# -2.net
KiCad netlist of a schematic drawn in Altium Designer
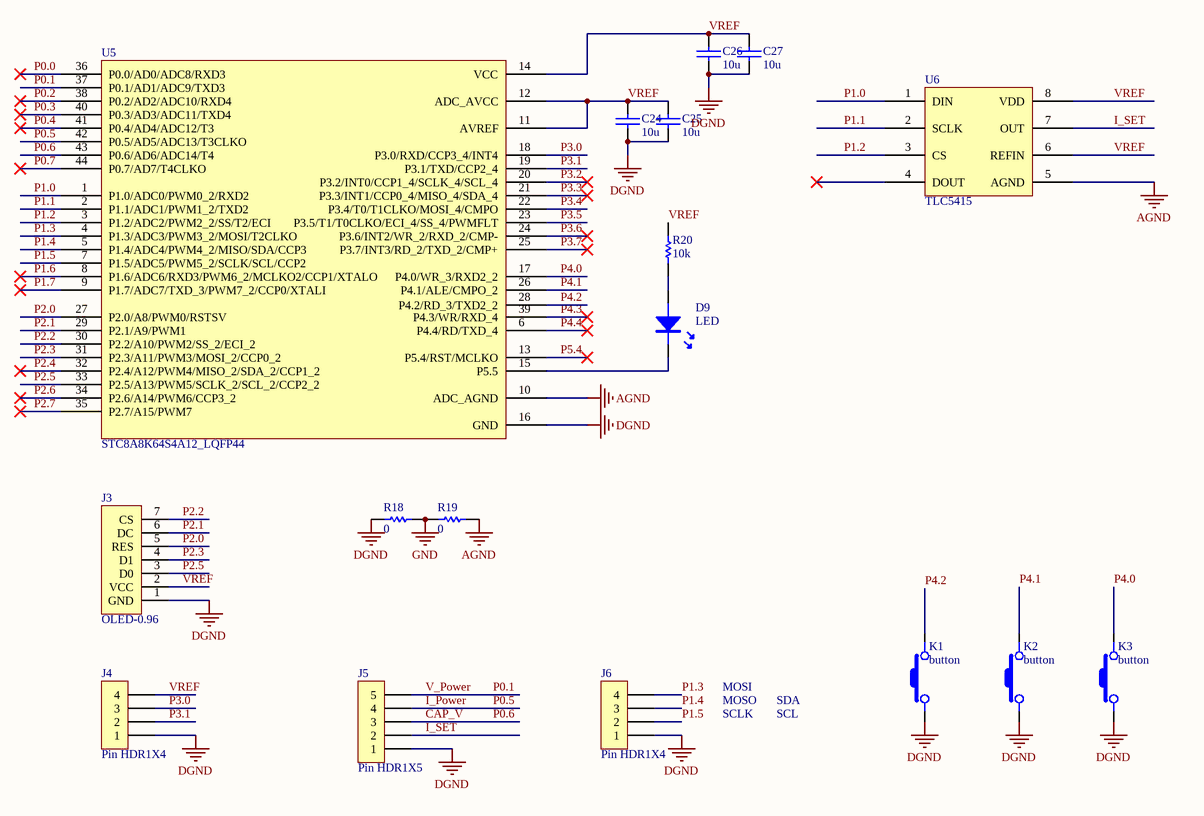
[diagram p0: 充电二板-2.SchDoc]

(export (version "E")
  (design (tool "Eeschema 10.0.6"))
  (components
    (comp (ref "C24")
      (value "10u")
      (footprint "0603C")
      (description "无极性电容")
      (libsource (lib "电容") (part "CAP"))
    )
    (comp (ref "C25")
      (value "10u")
      (footprint "0603C")
      (description "无极性电容")
      (libsource (lib "电容") (part "CAP"))
    )
    (comp (ref "C26")
      (value "10u")
      (footprint "0603C")
      (description "无极性电容")
      (libsource (lib "电容") (part "CAP"))
    )
    (comp (ref "C27")
      (value "10u")
      (footprint "0603C")
      (description "无极性电容")
      (libsource (lib "电容") (part "CAP"))
    )
    (comp (ref "D9") (value "LED") (footprint "LED-0603W") (libsource (lib "LED") (part "LED")))
    (comp (ref "J3")
      (value "OLED-0.96")
      (footprint "OLED-0.96")
      (libsource (lib "KEA电磁专用") (part "OLED-0.96"))
    )
    (comp (ref "J4")
      (value "Pin HDR1X4")
      (footprint "Pin HDR1X4/2.54mm-S")
      (libsource (lib "排针") (part "Pin HDR1X4"))
    )
    (comp (ref "J5")
      (value "Pin HDR1X5")
      (footprint "Pin HDR1X5/2.54mm-S")
      (libsource (lib "排针") (part "Pin HDR1X5"))
    )
    (comp (ref "J6")
      (value "Pin HDR1X4")
      (footprint "Pin HDR1X4/2.54mm-S")
      (libsource (lib "排针") (part "Pin HDR1X4"))
    )
    (comp (ref "K1") (value "button") (footprint "button") (libsource (lib "charge") (part "button")))
    (comp (ref "K2") (value "button") (footprint "button") (libsource (lib "charge") (part "button")))
    (comp (ref "K3") (value "button") (footprint "button") (libsource (lib "charge") (part "button")))
    (comp (ref "R18") (value "0") (footprint "0603R") (libsource (lib "电阻") (part "RES")))
    (comp (ref "R19") (value "0") (footprint "0603R") (libsource (lib "电阻") (part "RES")))
    (comp (ref "R20") (value "10k") (footprint "0603R") (libsource (lib "电阻") (part "RES")))
    (comp (ref "U5")
      (value "STC8A8K64S4A12_LQFP44")
      (footprint "LQFP144")
      (libsource (lib "charge") (part "STC8A8K64S4A12_LQFP44"))
    )
    (comp (ref "U6") (value "TLC5415") (footprint "TLC5415") (libsource (lib "charge") (part "TLC5415")))
  )
  (nets
    (net (code "1") (name "/CAP_V") (class "Default")
      (node (ref "J5") (pin "3") (pinfunction "3_3") (pintype "passive"))
      (node (ref "U5") (pin "43") (pinfunction "P0.6/AD6/ADC14/T4_43") (pintype "passive"))
    )
    (net (code "2") (name "/I_Power") (class "Default")
      (node (ref "J5") (pin "4") (pinfunction "4_4") (pintype "passive"))
      (node (ref "U5") (pin "42") (pinfunction "P0.5/AD5/ADC13/T3CLKO_42") (pintype "passive"))
    )
    (net (code "3") (name "/I_SET") (class "Default")
      (node (ref "J5") (pin "2") (pinfunction "2_2") (pintype "passive"))
      (node (ref "U6") (pin "7") (pinfunction "OUT_7") (pintype "passive"))
    )
    (net (code "4") (name "/P0.0") (class "Default")
      (node (ref "U5") (pin "36") (pinfunction "P0.0/AD0/ADC8/RXD3_36") (pintype "passive+no_connect"))
    )
    (net (code "5") (name "/P0.1") (class "Default")
      (node (ref "J5") (pin "5") (pinfunction "5_5") (pintype "passive"))
      (node (ref "U5") (pin "37") (pinfunction "P0.1/AD1/ADC9/TXD3_37") (pintype "passive"))
    )
    (net (code "6") (name "/P0.2") (class "Default")
      (node (ref "U5") (pin "38") (pinfunction "P0.2/AD2/ADC10/RXD4_38") (pintype "passive+no_connect"))
    )
    (net (code "7") (name "/P0.3") (class "Default")
      (node (ref "U5") (pin "40") (pinfunction "P0.3/AD3/ADC11/TXD4_40") (pintype "passive+no_connect"))
    )
    (net (code "8") (name "/P0.4") (class "Default")
      (node (ref "U5") (pin "41") (pinfunction "P0.4/AD4/ADC12/T3_41") (pintype "passive+no_connect"))
    )
    (net (code "9") (name "/P0.7") (class "Default")
      (node (ref "U5") (pin "44") (pinfunction "P0.7/AD7/T4CLKO_44") (pintype "passive+no_connect"))
    )
    (net (code "10") (name "/P1.0") (class "Default")
      (node (ref "U5") (pin "1") (pinfunction "P1.0/ADC0/PWM0_2/RXD2_1") (pintype "passive"))
      (node (ref "U6") (pin "1") (pinfunction "DIN_1") (pintype "passive"))
    )
    (net (code "11") (name "/P1.1") (class "Default")
      (node (ref "U5") (pin "2") (pinfunction "P1.1/ADC1/PWM1_2/TXD2_2") (pintype "passive"))
      (node (ref "U6") (pin "2") (pinfunction "SCLK_2") (pintype "passive"))
    )
    (net (code "12") (name "/P1.2") (class "Default")
      (node (ref "U5") (pin "3") (pinfunction "P1.2/ADC2/PWM2_2/SS/T2/ECI_3") (pintype "passive"))
      (node (ref "U6") (pin "3") (pinfunction "CS_3") (pintype "passive"))
    )
    (net (code "13") (name "/P1.3") (class "Default")
      (node (ref "J6") (pin "4") (pinfunction "4_4") (pintype "passive"))
      (node (ref "U5") (pin "4") (pinfunction "P1.3/ADC3/PWM3_2/MOSI/T2CLKO_4") (pintype "passive"))
    )
    (net (code "14") (name "/P1.4") (class "Default")
      (node (ref "J6") (pin "3") (pinfunction "3_3") (pintype "passive"))
      (node (ref "U5") (pin "5") (pinfunction "P1.4/ADC4/PWM4_2/MISO/SDA/CCP3_5") (pintype "passive"))
    )
    (net (code "15") (name "/P1.5") (class "Default")
      (node (ref "J6") (pin "2") (pinfunction "2_2") (pintype "passive"))
      (node (ref "U5") (pin "7") (pinfunction "P1.5/ADC5/PWM5_2/SCLK/SCL/CCP2_7") (pintype "passive"))
    )
    (net (code "16") (name "/P1.6") (class "Default")
      (node (ref "U5") (pin "8") (pinfunction "P1.6/ADC6/RXD3/PWM6_2/MCLKO2/CCP1/XTALO_8") (pintype "passive+no_connect"))
    )
    (net (code "17") (name "/P1.7") (class "Default")
      (node (ref "U5") (pin "9") (pinfunction "P1.7/ADC7/TXD_3/PWM7_2/CCP0/XTALI_9") (pintype "passive+no_connect"))
    )
    (net (code "18") (name "/P2.0") (class "Default")
      (node (ref "J3") (pin "5") (pinfunction "RES_5") (pintype "passive"))
      (node (ref "U5") (pin "27") (pinfunction "P2.0/A8/PWM0/RSTSV_27") (pintype "passive"))
    )
    (net (code "19") (name "/P2.1") (class "Default")
      (node (ref "J3") (pin "6") (pinfunction "DC_6") (pintype "passive"))
      (node (ref "U5") (pin "29") (pinfunction "P2.1/A9/PWM1_29") (pintype "passive"))
    )
    (net (code "20") (name "/P2.2") (class "Default")
      (node (ref "J3") (pin "7") (pinfunction "CS_7") (pintype "passive"))
      (node (ref "U5") (pin "30") (pinfunction "P2.2/A10/PWM2/SS_2/ECI_2_30") (pintype "passive"))
    )
    (net (code "21") (name "/P2.3") (class "Default")
      (node (ref "J3") (pin "4") (pinfunction "D1_4") (pintype "passive"))
      (node (ref "U5") (pin "31") (pinfunction "P2.3/A11/PWM3/MOSI_2/CCP0_2_31") (pintype "passive"))
    )
    (net (code "22") (name "/P2.4") (class "Default")
      (node (ref "U5") (pin "32") (pinfunction "P2.4/A12/PWM4/MISO_2/SDA_2/CCP1_2_32") (pintype "passive+no_connect"))
    )
    (net (code "23") (name "/P2.5") (class "Default")
      (node (ref "J3") (pin "3") (pinfunction "D0_3") (pintype "passive"))
      (node (ref "U5") (pin "33") (pinfunction "P2.5/A13/PWM5/SCLK_2/SCL_2/CCP2_2_33") (pintype "passive"))
    )
    (net (code "24") (name "/P2.6") (class "Default")
      (node (ref "U5") (pin "34") (pinfunction "P2.6/A14/PWM6/CCP3_2_34") (pintype "passive+no_connect"))
    )
    (net (code "25") (name "/P2.7") (class "Default")
      (node (ref "U5") (pin "35") (pinfunction "P2.7/A15/PWM7_35") (pintype "passive+no_connect"))
    )
    (net (code "26") (name "/P3.0") (class "Default")
      (node (ref "J4") (pin "3") (pinfunction "3_3") (pintype "passive"))
      (node (ref "U5") (pin "18") (pinfunction "P3.0/RXD/CCP3_4/INT4_18") (pintype "passive"))
    )
    (net (code "27") (name "/P3.1") (class "Default")
      (node (ref "J4") (pin "2") (pinfunction "2_2") (pintype "passive"))
      (node (ref "U5") (pin "19") (pinfunction "P3.1/TXD/CCP2_4_19") (pintype "passive"))
    )
    (net (code "28") (name "/P3.2") (class "Default")
      (node (ref "U5") (pin "20") (pinfunction "P3.2/INT0/CCP1_4/SCLK_4/SCL_4_20") (pintype "passive+no_connect"))
    )
    (net (code "29") (name "/P3.3") (class "Default")
      (node (ref "U5") (pin "21") (pinfunction "P3.3/INT1/CCP0_4/MISO_4/SDA_4_21") (pintype "passive+no_connect"))
    )
    (net (code "30") (name "/P3.4") (class "Default")
      (node (ref "U5") (pin "22") (pinfunction "P3.4/T0/T1CLKO/MOSI_4/CMPO_22") (pintype "passive"))
    )
    (net (code "31") (name "/P3.5") (class "Default")
      (node (ref "U5") (pin "23") (pinfunction "P3.5/T1/T0CLKO/ECI_4/SS_4/PWMFLT_23") (pintype "passive"))
    )
    (net (code "32") (name "/P3.6") (class "Default")
      (node (ref "U5") (pin "24") (pinfunction "P3.6/INT2/WR_2/RXD_2/CMP-_24") (pintype "passive+no_connect"))
    )
    (net (code "33") (name "/P3.7") (class "Default")
      (node (ref "U5") (pin "25") (pinfunction "P3.7/INT3/RD_2/TXD_2/CMP+_25") (pintype "passive+no_connect"))
    )
    (net (code "34") (name "/P4.0") (class "Default")
      (node (ref "K3") (pin "2") (pintype "passive"))
      (node (ref "U5") (pin "17") (pinfunction "P4.0/WR_3/RXD2_2_17") (pintype "passive"))
    )
    (net (code "35") (name "/P4.1") (class "Default")
      (node (ref "K2") (pin "2") (pintype "passive"))
      (node (ref "U5") (pin "26") (pinfunction "P4.1/ALE/CMPO_2_26") (pintype "passive"))
    )
    (net (code "36") (name "/P4.2") (class "Default")
      (node (ref "K1") (pin "2") (pintype "passive"))
      (node (ref "U5") (pin "28") (pinfunction "P4.2/RD_3/TXD2_2_28") (pintype "passive"))
    )
    (net (code "37") (name "/P4.3") (class "Default")
      (node (ref "U5") (pin "39") (pinfunction "P4.3/WR/RXD_4_39") (pintype "passive+no_connect"))
    )
    (net (code "38") (name "/P4.4") (class "Default")
      (node (ref "U5") (pin "6") (pinfunction "P4.4/RD/TXD_4_6") (pintype "passive+no_connect"))
    )
    (net (code "39") (name "/P5.4") (class "Default")
      (node (ref "U5") (pin "13") (pinfunction "P5.4/RST/MCLKO_13") (pintype "passive+no_connect"))
    )
    (net (code "40") (name "/VREF") (class "Default")
      (node (ref "C24") (pin "2") (pinfunction "2_2") (pintype "passive"))
      (node (ref "C25") (pin "2") (pinfunction "2_2") (pintype "passive"))
      (node (ref "C26") (pin "2") (pinfunction "2_2") (pintype "passive"))
      (node (ref "C27") (pin "2") (pinfunction "2_2") (pintype "passive"))
      (node (ref "J3") (pin "2") (pinfunction "VCC_2") (pintype "passive"))
      (node (ref "J4") (pin "4") (pinfunction "4_4") (pintype "passive"))
      (node (ref "R20") (pin "1") (pinfunction "1_1") (pintype "passive"))
      (node (ref "U5") (pin "11") (pinfunction "AVREF_11") (pintype "passive"))
      (node (ref "U5") (pin "12") (pinfunction "ADC_AVCC_12") (pintype "passive"))
      (node (ref "U5") (pin "14") (pinfunction "VCC_14") (pintype "passive"))
      (node (ref "U6") (pin "6") (pinfunction "REFIN_6") (pintype "passive"))
      (node (ref "U6") (pin "8") (pinfunction "VDD_8") (pintype "passive"))
    )
    (net (code "41") (name "AGND") (class "Default")
      (node (ref "R19") (pin "2") (pinfunction "2_2") (pintype "passive"))
      (node (ref "U5") (pin "10") (pinfunction "ADC_AGND_10") (pintype "passive"))
      (node (ref "U6") (pin "5") (pinfunction "AGND_5") (pintype "passive"))
    )
    (net (code "42") (name "DGND") (class "Default")
      (node (ref "C24") (pin "1") (pinfunction "1_1") (pintype "passive"))
      (node (ref "C25") (pin "1") (pinfunction "1_1") (pintype "passive"))
      (node (ref "C26") (pin "1") (pinfunction "1_1") (pintype "passive"))
      (node (ref "C27") (pin "1") (pinfunction "1_1") (pintype "passive"))
      (node (ref "J3") (pin "1") (pinfunction "GND_1") (pintype "passive"))
      (node (ref "J4") (pin "1") (pinfunction "1_1") (pintype "passive"))
      (node (ref "J5") (pin "1") (pinfunction "1_1") (pintype "passive"))
      (node (ref "J6") (pin "1") (pinfunction "1_1") (pintype "passive"))
      (node (ref "K1") (pin "1") (pintype "passive"))
      (node (ref "K2") (pin "1") (pintype "passive"))
      (node (ref "K3") (pin "1") (pintype "passive"))
      (node (ref "R18") (pin "1") (pinfunction "1_1") (pintype "passive"))
      (node (ref "U5") (pin "16") (pinfunction "GND_16") (pintype "passive"))
    )
    (net (code "43") (name "GND") (class "Default")
      (node (ref "R18") (pin "2") (pinfunction "2_2") (pintype "passive"))
      (node (ref "R19") (pin "1") (pinfunction "1_1") (pintype "passive"))
    )
    (net (code "44") (name "Net-(D9-PadA)") (class "Default")
      (node (ref "D9") (pin "A") (pinfunction "A_A") (pintype "passive"))
      (node (ref "R20") (pin "2") (pinfunction "2_2") (pintype "passive"))
    )
    (net (code "45") (name "Net-(U5-P5.5)") (class "Default")
      (node (ref "D9") (pin "K") (pinfunction "K_K") (pintype "passive"))
      (node (ref "U5") (pin "15") (pinfunction "P5.5_15") (pintype "passive"))
    )
    (net (code "46") (name "unconnected-(U6-DOUT-Pad4)") (class "Default")
      (node (ref "U6") (pin "4") (pinfunction "DOUT_4") (pintype "passive+no_connect"))
    )
  )
)
